# VI_Sensors.net
KiCad netlist of a schematic drawn in Altium Designer
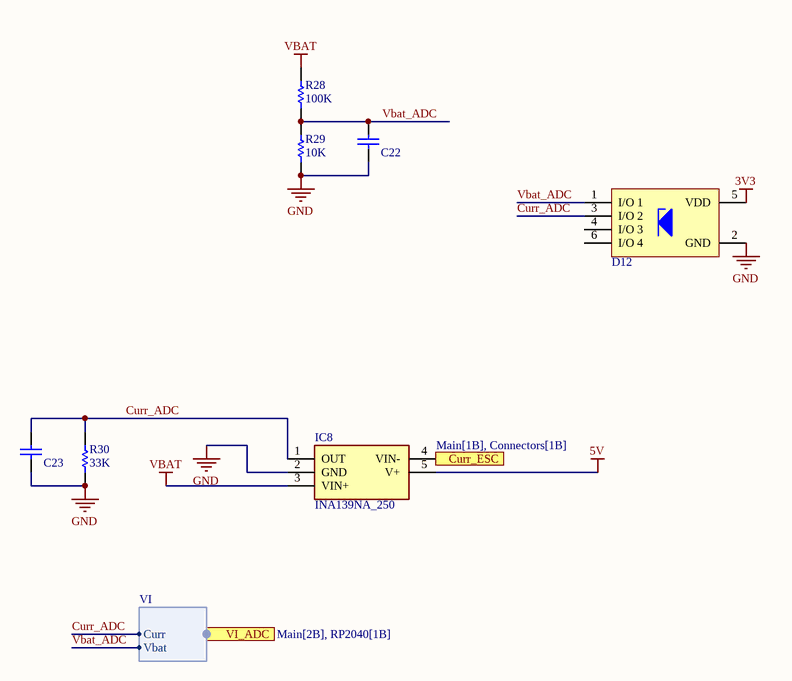
[diagram p0: VI Sensors.SchDoc]

(export (version "E")
  (design (tool "Eeschema 10.0.6"))
  (components
    (comp (ref "C22")
      (value "1µF")
      (footprint "WCAP-CSGP_0603_L1.6W0.8H0.8_Reflow")
      (description "WCAP-CSGP Multilayer Ceramic Chip Capacitor, General Purpose, size 0603, X5R, 1µF, 16VDC")
      (fields
        (field (name "MANUFACTURER PART NUMBER") "885012106017")
        (field (name "MANUFACTURER") "Wurth Elektronik")
      )
      (libsource (lib "Altium_WCAP-CSGP (rev22e)") (part "885012106017"))
    )
    (comp (ref "C23")
      (value "1µF")
      (footprint "WCAP-CSGP_0603_L1.6W0.8H0.8_Reflow")
      (description "WCAP-CSGP Multilayer Ceramic Chip Capacitor, General Purpose, size 0603, X5R, 1µF, 16VDC")
      (fields
        (field (name "MANUFACTURER PART NUMBER") "885012106017")
        (field (name "MANUFACTURER") "Wurth Elektronik")
      )
      (libsource (lib "Altium_WCAP-CSGP (rev22e)") (part "885012106017"))
    )
    (comp (ref "D12")
      (value "3.3V")
      (footprint "WE-TVS_SOT23-6L")
      (description "Shenzhen JingYang TT0514VL")
      (fields
        (field (name "MANUFACTURER PART NUMBER") "824015043")
        (field (name "MANUFACTURER") "Wurth Elektronik")
      )
      (libsource (lib "Altium_WE-TVS (rev22b)") (part "824015043"))
    )
    (comp (ref "IC8")
      (value "INA139NA_250")
      (footprint "Custom Components:SOT95P280X145-5N")
      (description "Integrated Circuit")
      (fields
        (field (name "MANUFACTURER_PART_NUMBER") "INA139NA/250")
        (field (name "MOUSER PART NUMBER") "595-INA139NA/250")
      )
      (libsource (lib "*") (part "INA139NA_250"))
    )
    (comp (ref "R28")
      (value "100K")
      (footprint "RESC0603(1608)_N")
      (description "Chipwiderstand, SMD, Baureihe MC, 1%")
      (fields (field (name "MANUFACTURER") "Multicomp"))
      (libsource (lib "Standardbauteile") (part "Res 100K"))
    )
    (comp (ref "R29")
      (value "10K")
      (footprint "RESC0603(1608)_N")
      (description "Chipwiderstand, SMD, Baureihe MC, 1%")
      (fields (field (name "MANUFACTURER") "Multicomp"))
      (libsource (lib "Standardbauteile") (part "Res 10K"))
    )
    (comp (ref "R30")
      (value "33K")
      (footprint "RESC0603(1608)_N")
      (description "Chipwiderstand, SMD, Baureihe MC, 1%")
      (fields (field (name "MANUFACTURER") "Multicomp"))
      (libsource (lib "Standardbauteile") (part "Res 33K"))
    )
  )
  (nets
    (net (code "2") (name "/Curr_ADC") (class "Default")
      (node (ref "C23") (pin "2") (pinfunction "2_2") (pintype "passive"))
      (node (ref "D12") (pin "3") (pinfunction "I/O_2_3") (pintype "passive"))
      (node (ref "IC8") (pin "1") (pinfunction "OUT_1") (pintype "passive"))
      (node (ref "R30") (pin "2") (pinfunction "2_2") (pintype "passive"))
    )
    (net (code "3") (name "/Curr_ESC") (class "Default")
      (node (ref "IC8") (pin "4") (pinfunction "VIN-_4") (pintype "passive"))
    )
    (net (code "4") (name "/Vbat_ADC") (class "Default")
      (node (ref "C22") (pin "2") (pinfunction "2_2") (pintype "passive"))
      (node (ref "D12") (pin "1") (pinfunction "I/O_1_1") (pintype "passive"))
      (node (ref "R28") (pin "1") (pinfunction "1_1") (pintype "passive"))
      (node (ref "R29") (pin "2") (pinfunction "2_2") (pintype "passive"))
    )
    (net (code "6") (name "3V3") (class "Default")
      (node (ref "D12") (pin "5") (pinfunction "VDD_5") (pintype "passive"))
    )
    (net (code "7") (name "5V") (class "Default")
      (node (ref "IC8") (pin "5") (pinfunction "V+_5") (pintype "passive"))
    )
    (net (code "8") (name "GND") (class "Default")
      (node (ref "C22") (pin "1") (pinfunction "1_1") (pintype "passive"))
      (node (ref "C23") (pin "1") (pinfunction "1_1") (pintype "passive"))
      (node (ref "D12") (pin "2") (pinfunction "GND_2") (pintype "passive"))
      (node (ref "IC8") (pin "2") (pinfunction "GND_2") (pintype "passive"))
      (node (ref "R29") (pin "1") (pinfunction "1_1") (pintype "passive"))
      (node (ref "R30") (pin "1") (pinfunction "1_1") (pintype "passive"))
    )
    (net (code "9") (name "VBAT") (class "Default")
      (node (ref "IC8") (pin "3") (pinfunction "VIN+_3") (pintype "passive"))
      (node (ref "R28") (pin "2") (pinfunction "2_2") (pintype "passive"))
    )
    (net (code "10") (name "unconnected-(D12-I{slash}O_3-Pad4)") (class "Default")
      (node (ref "D12") (pin "4") (pinfunction "I/O_3_4") (pintype "passive"))
    )
    (net (code "11") (name "unconnected-(D12-I{slash}O_4-Pad6)") (class "Default")
      (node (ref "D12") (pin "6") (pinfunction "I/O_4_6") (pintype "passive"))
    )
  )
)
